# High_Fructose.net
KiCad netlist of a schematic drawn in EAGLE
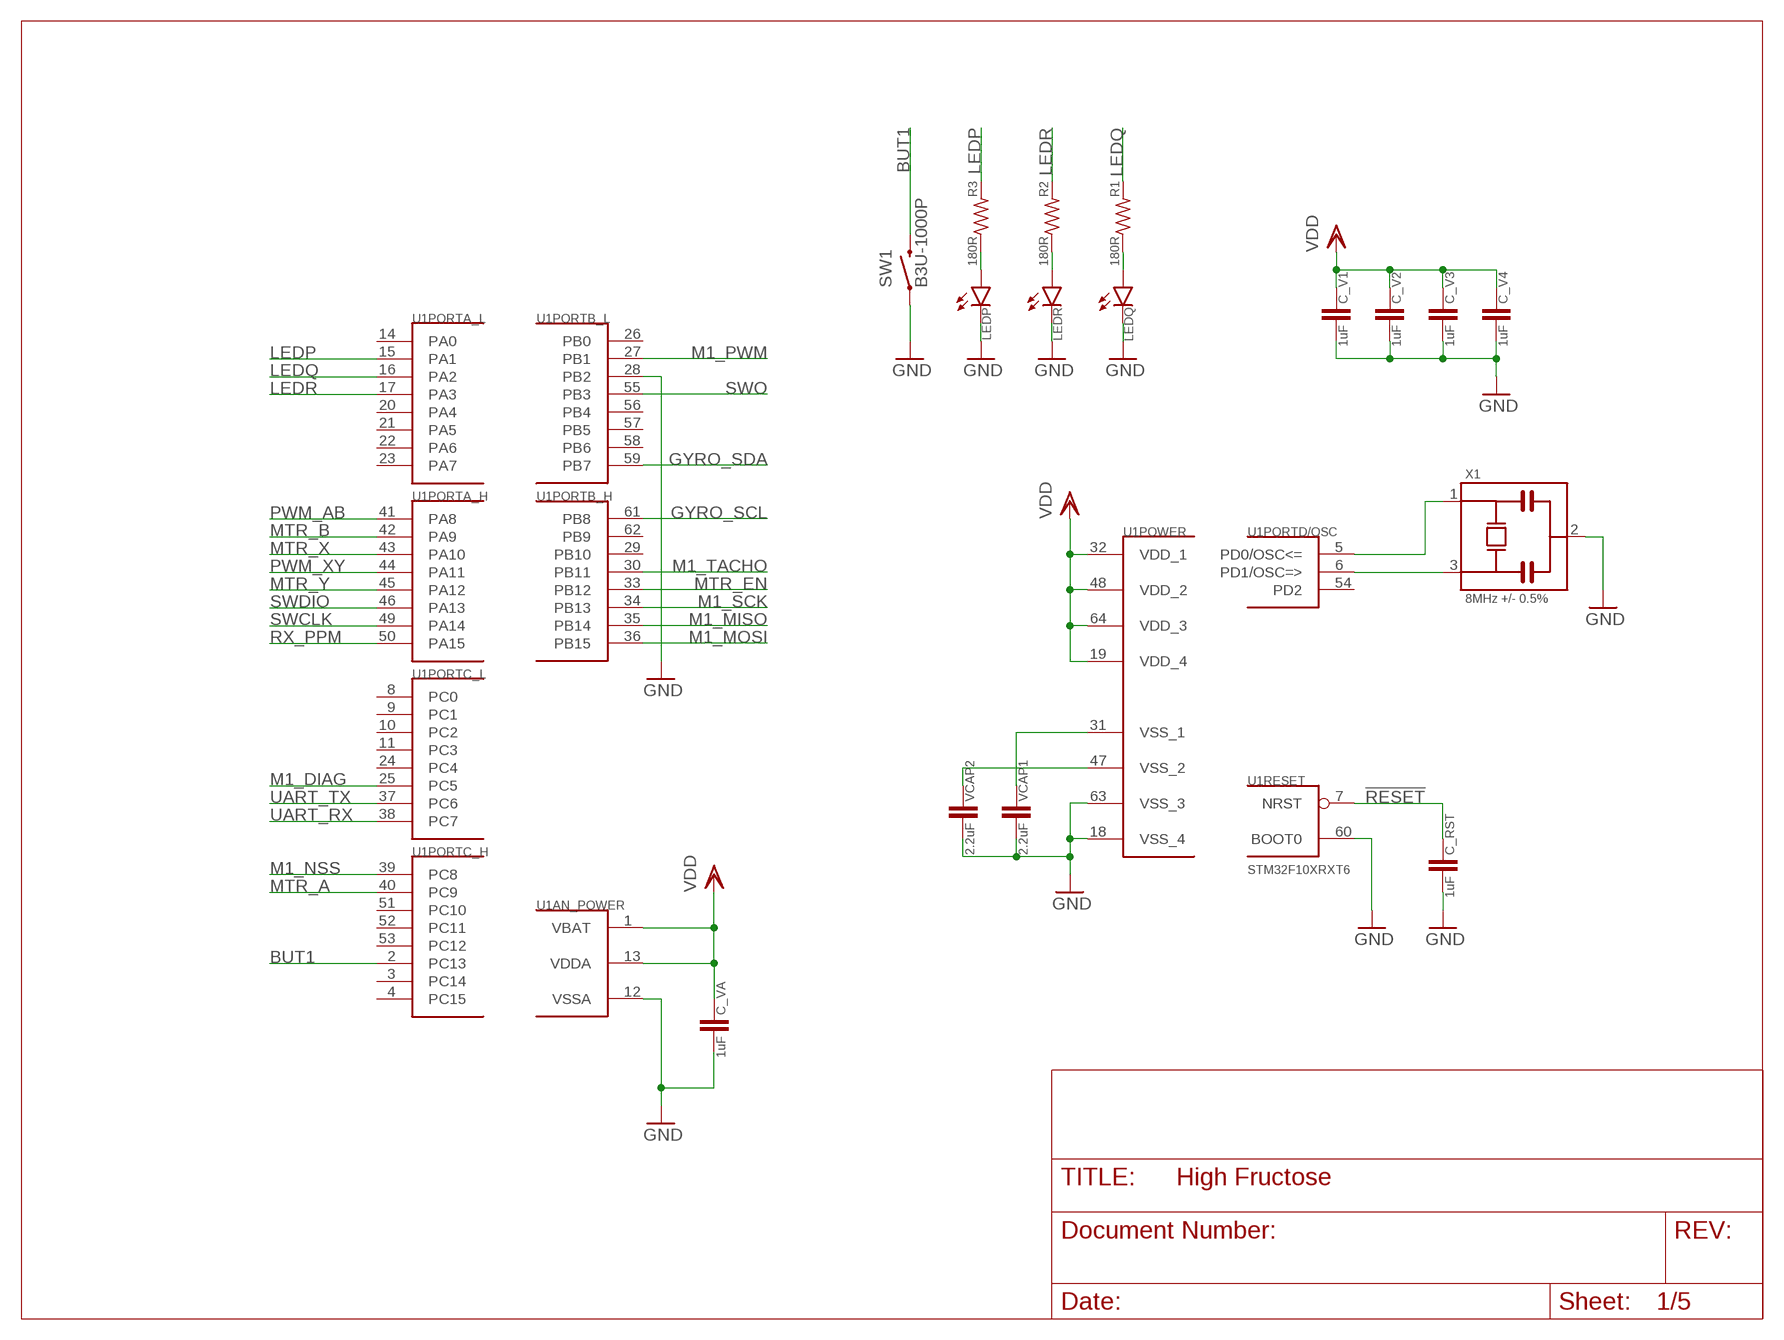
[diagram p0: schematic, sheet 1]
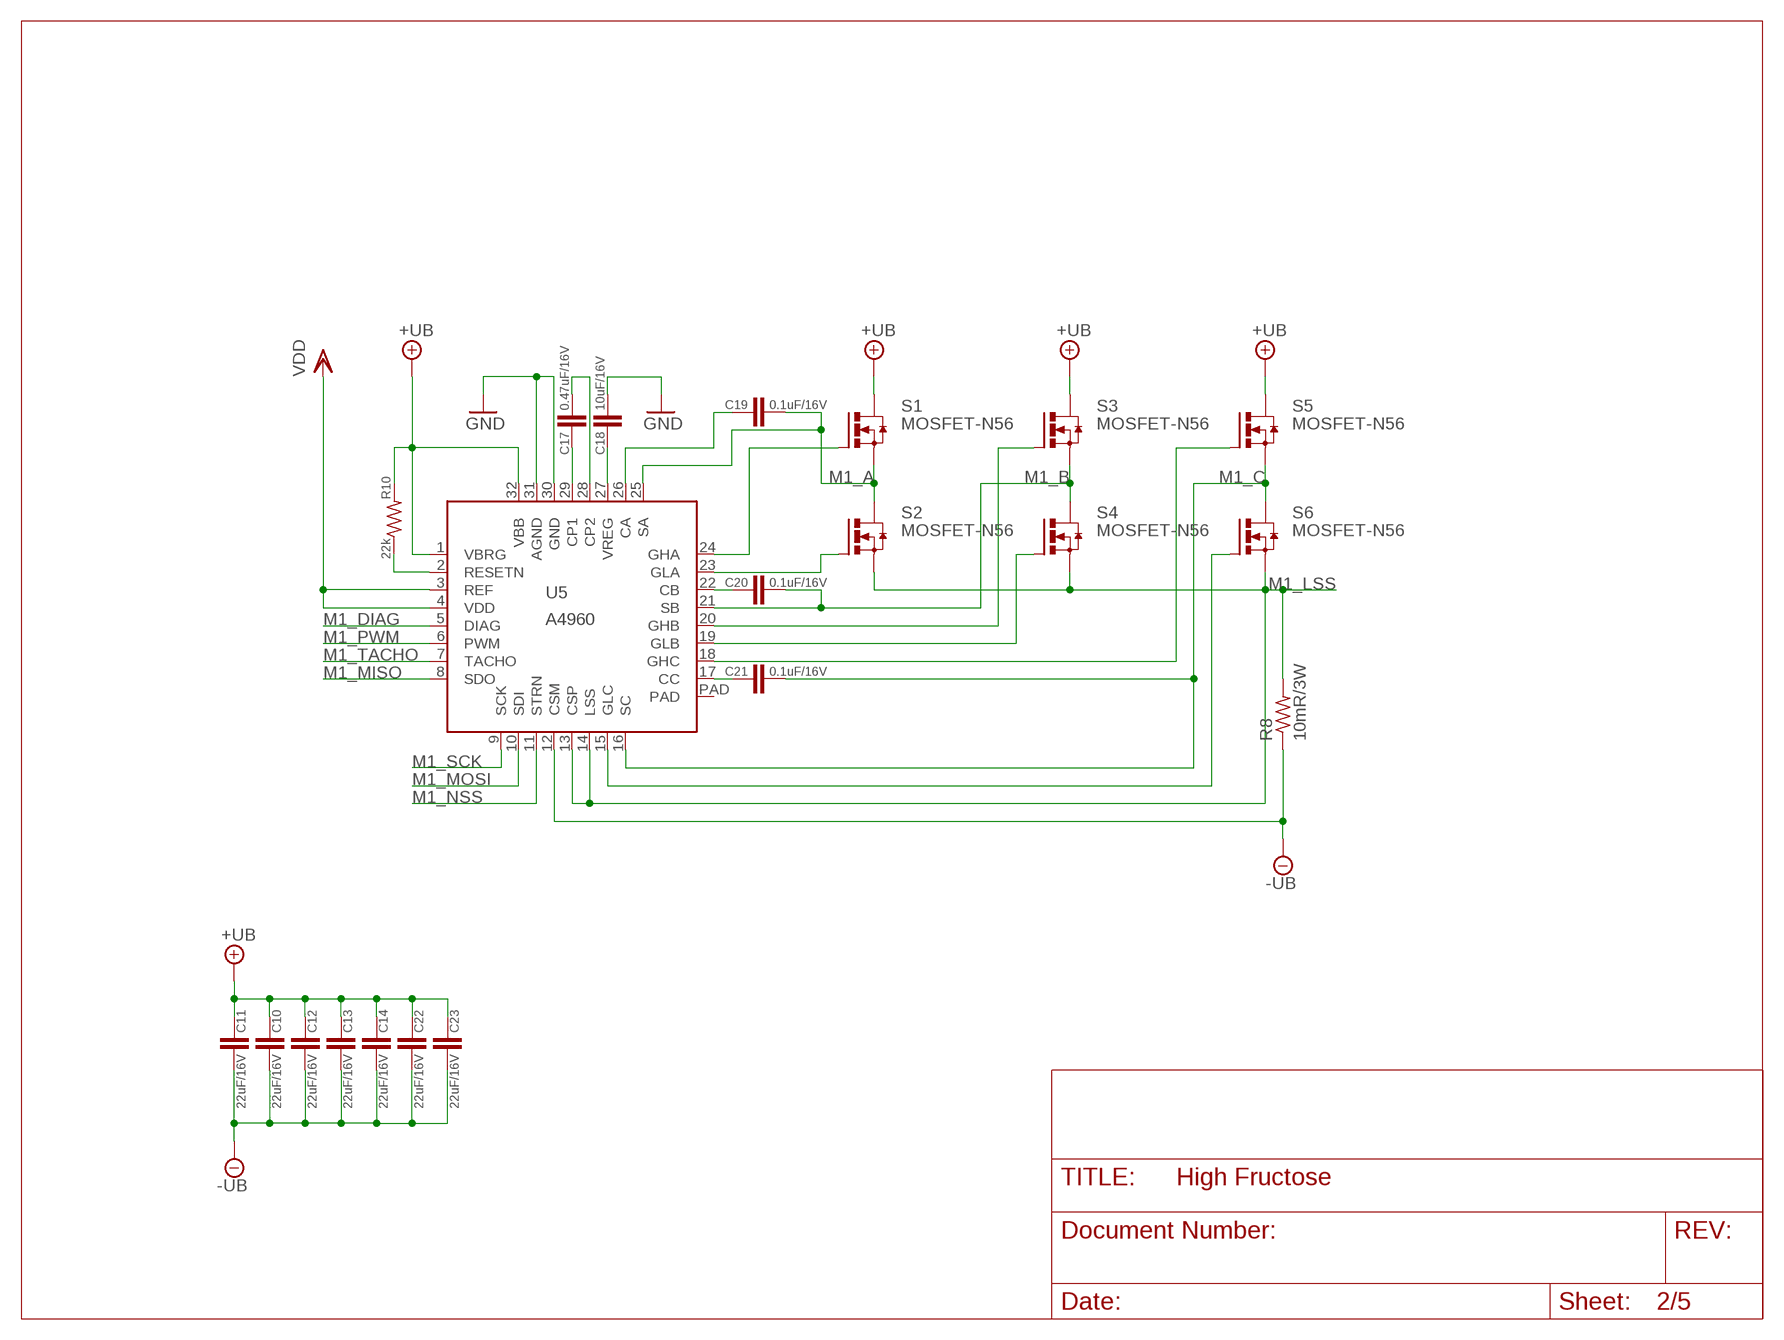
[diagram p1: schematic, sheet 2]
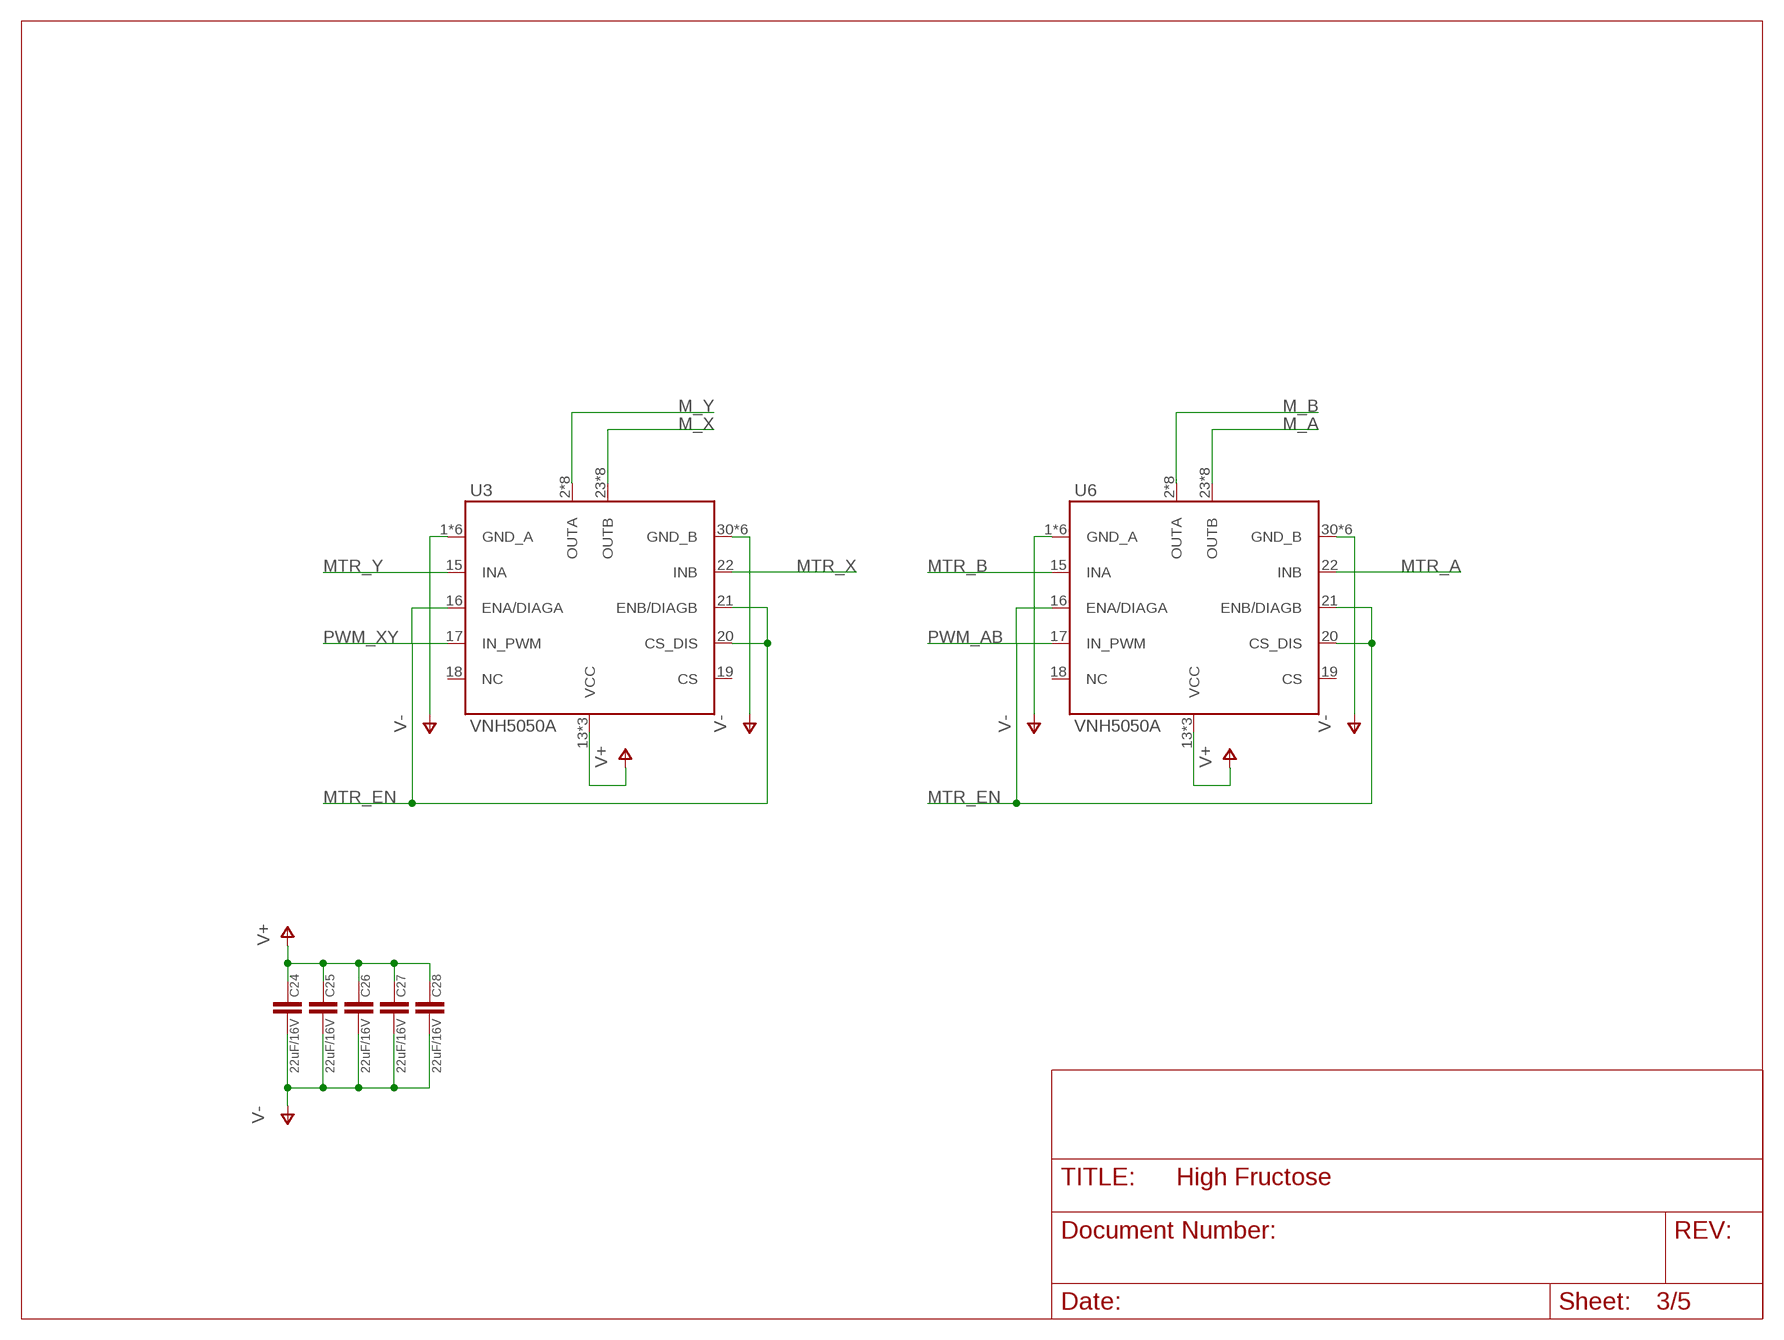
[diagram p2: schematic, sheet 3]
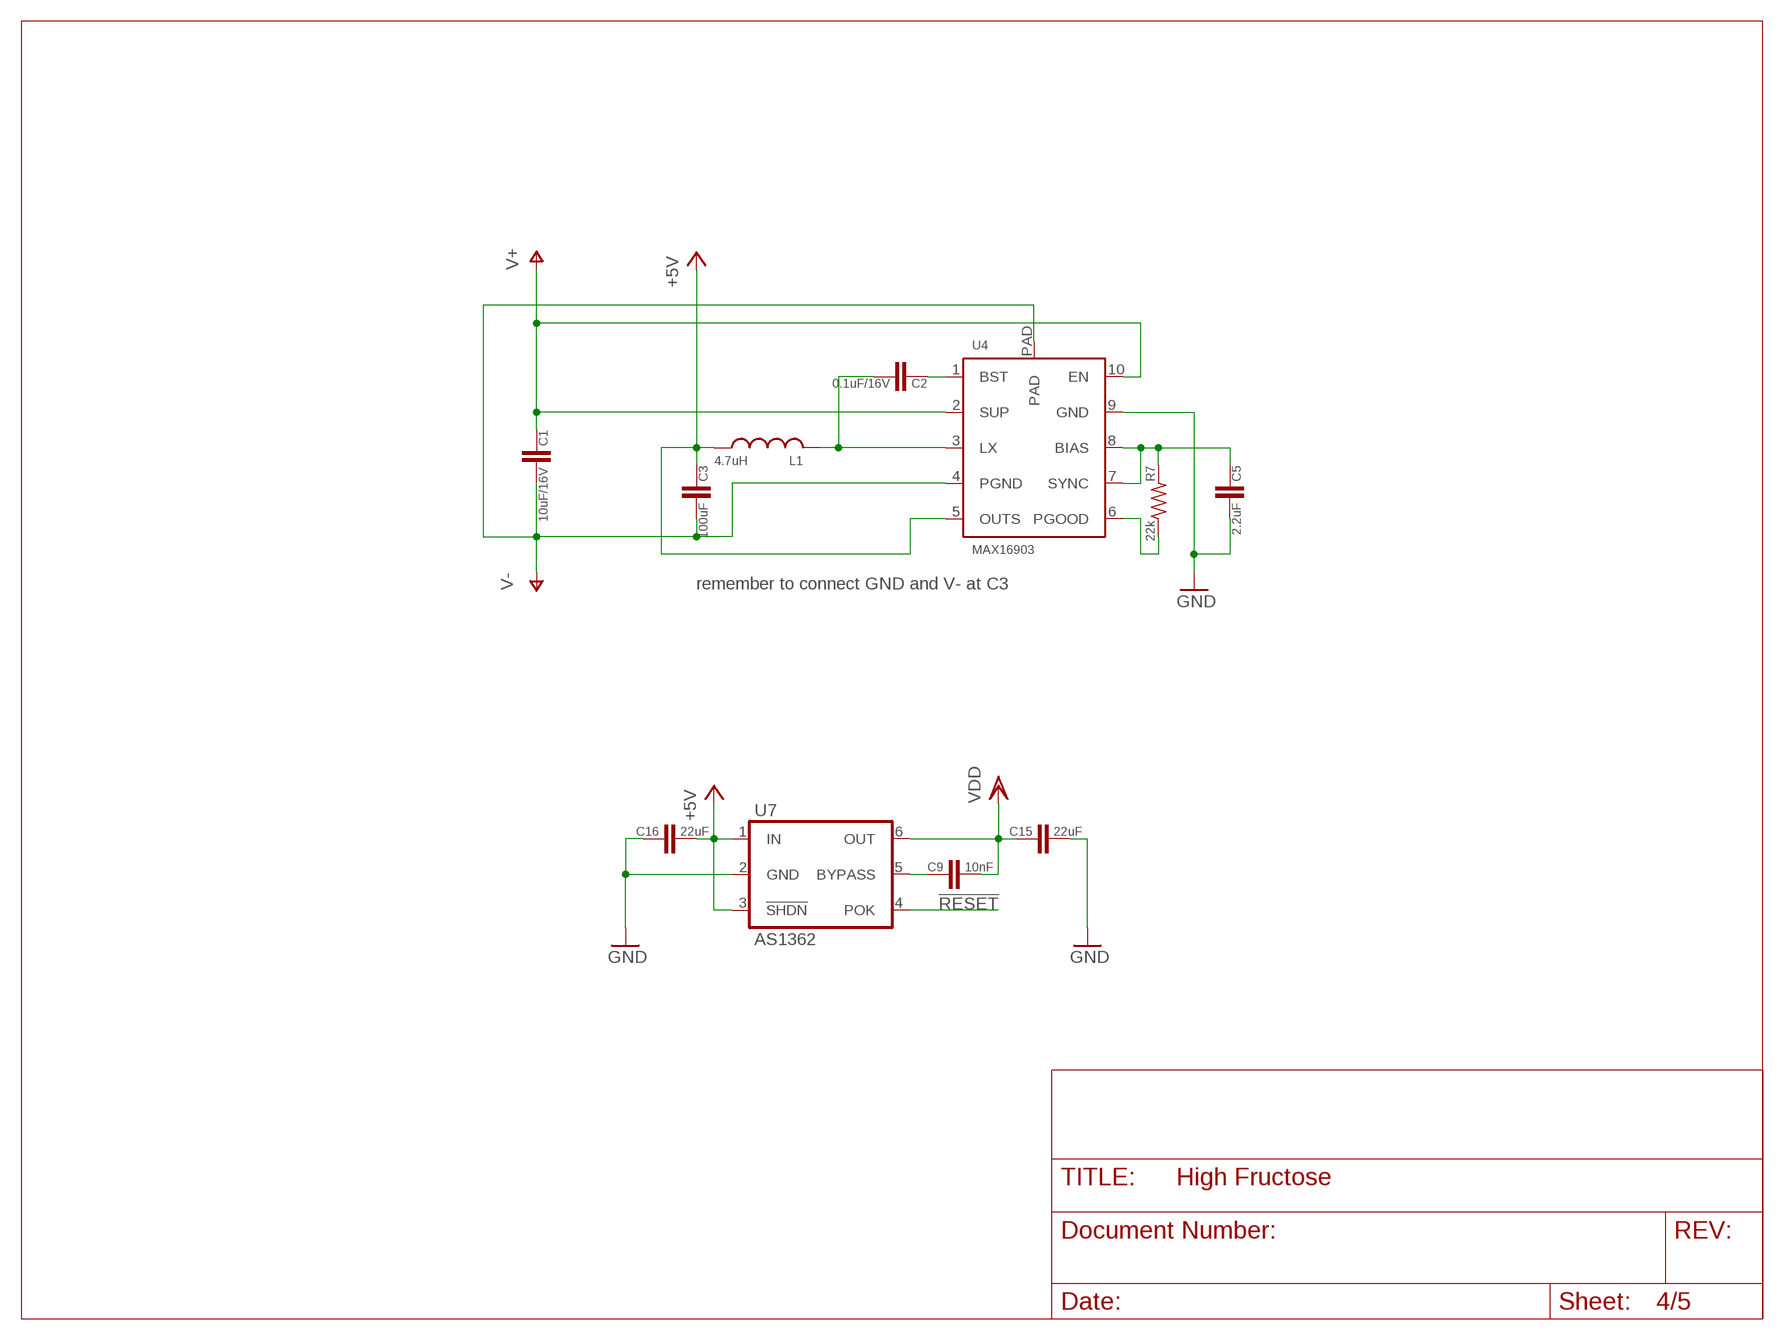
[diagram p3: schematic, sheet 4]
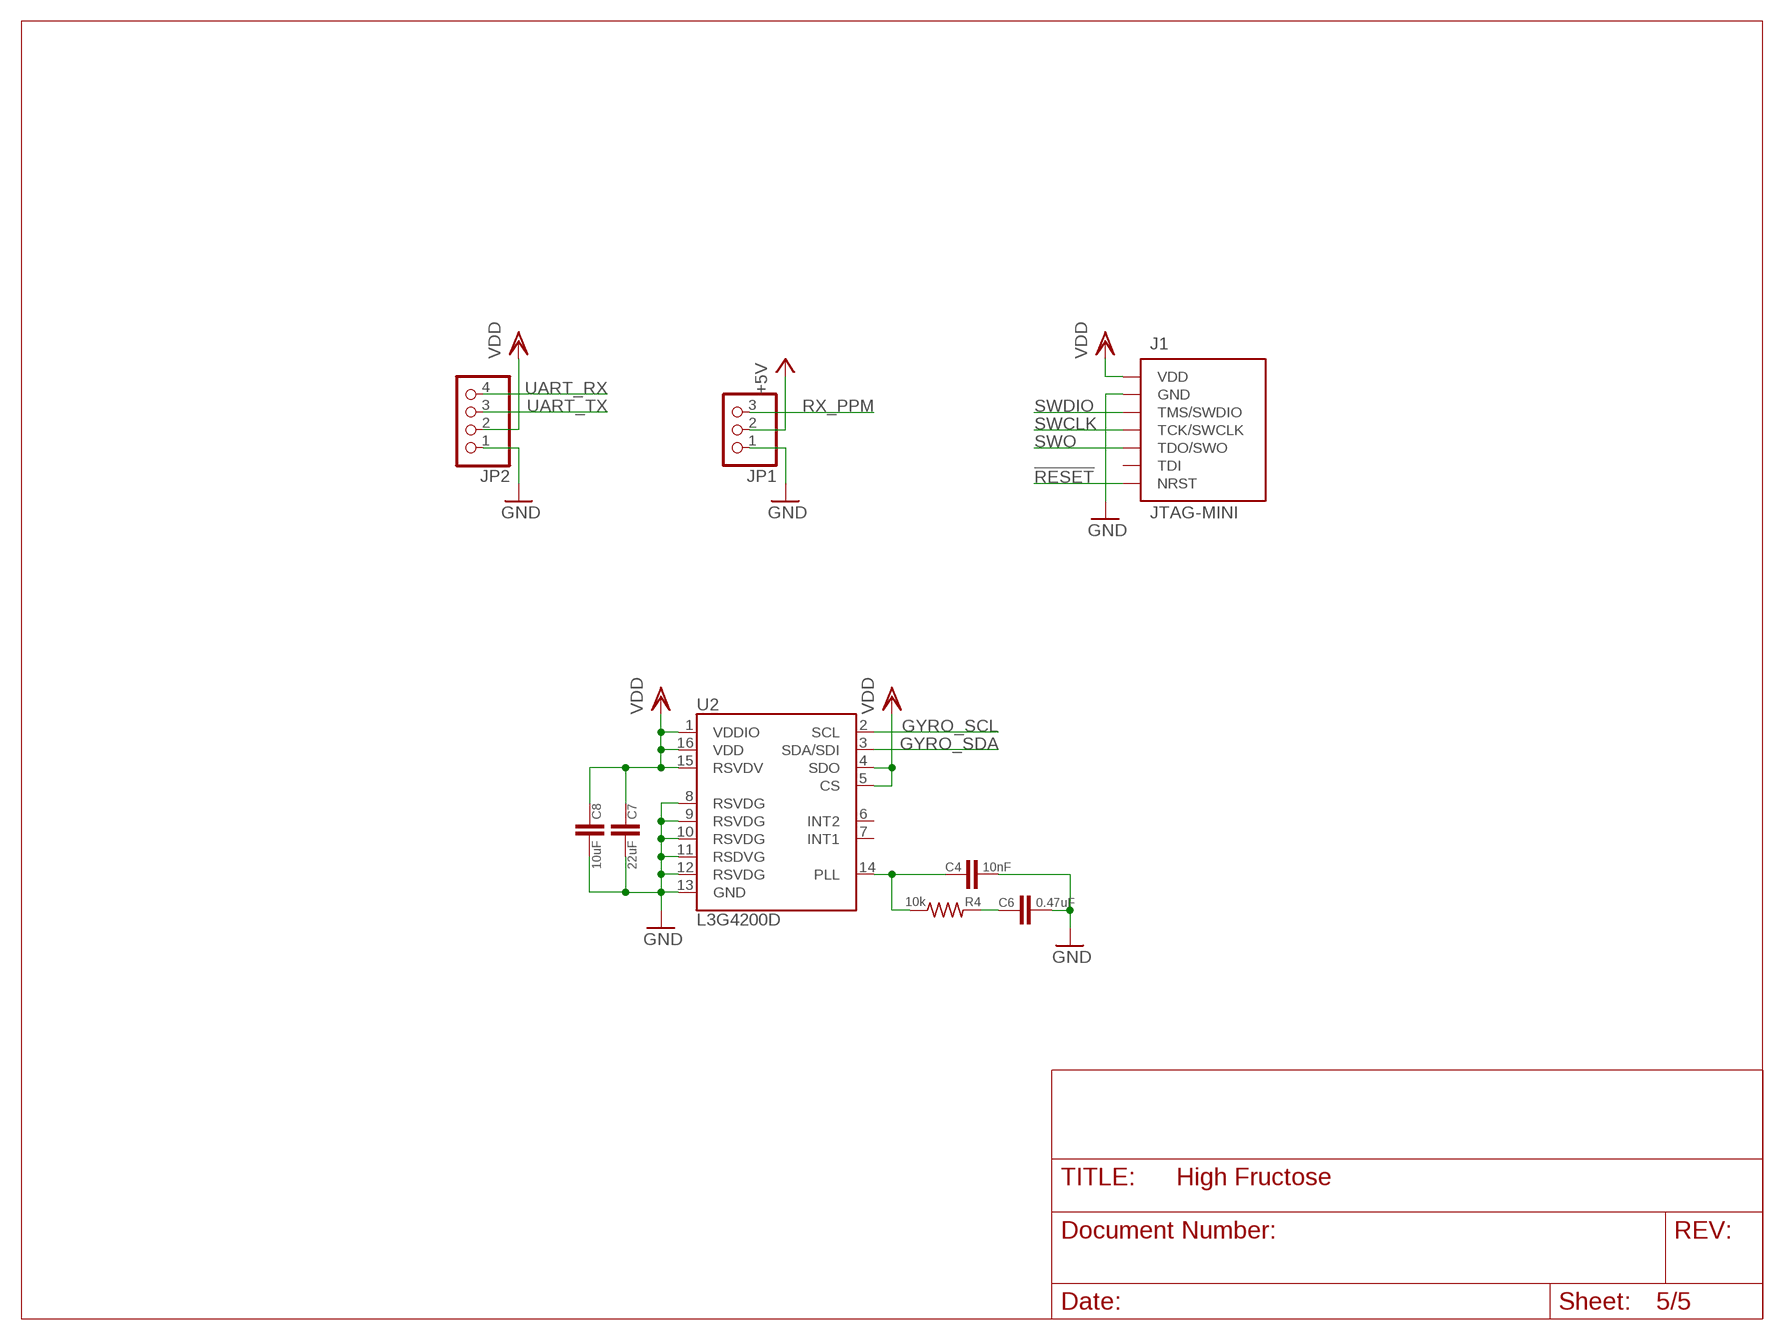
[diagram p4: schematic, sheet 5]

(export (version "E")
  (design (tool "Eeschema 10.0.6"))
  (components
    (comp (ref "C1")
      (value "10uF/16V")
      (footprint "eagle-import:0805")
      (libsource (lib "eagle-import") (part "C0805"))
    )
    (comp (ref "C2")
      (value "0.1uF/16V")
      (footprint "eagle-import:0603")
      (libsource (lib "eagle-import") (part "C0603"))
    )
    (comp (ref "C3")
      (value "100uF")
      (footprint "eagle-import:1206")
      (libsource (lib "eagle-import") (part "C1206"))
    )
    (comp (ref "C5")
      (value "2.2uF")
      (footprint "eagle-import:0603")
      (libsource (lib "eagle-import") (part "C0603"))
    )
    (comp (ref "C9")
      (value "10nF")
      (footprint "eagle-import:0603")
      (libsource (lib "eagle-import") (part "C0603"))
    )
    (comp (ref "C15")
      (value "22uF")
      (footprint "eagle-import:0805")
      (libsource (lib "eagle-import") (part "C0805"))
    )
    (comp (ref "C16")
      (value "22uF")
      (footprint "eagle-import:0805")
      (libsource (lib "eagle-import") (part "C0805"))
    )
    (comp (ref "L1")
      (value "4.7uH")
      (footprint "eagle-import:TAIYO-YUDEN_NR30")
      (libsource (lib "eagle-import") (part "L-US_NR30"))
    )
    (comp (ref "R7")
      (value "22k")
      (footprint "eagle-import:0603")
      (libsource (lib "eagle-import") (part "R0603"))
    )
    (comp (ref "U4")
      (value "MAX16903")
      (footprint "eagle-import:TDFN-10")
      (libsource (lib "eagle-import") (part "MAX16903"))
    )
    (comp (ref "U7")
      (value "AS1362")
      (footprint "eagle-import:SOT23-6")
      (libsource (lib "eagle-import") (part "AS1362"))
    )
    (comp (ref "C24")
      (value "22uF/16V")
      (footprint "eagle-import:1206")
      (libsource (lib "eagle-import") (part "C1206"))
    )
    (comp (ref "C25")
      (value "22uF/16V")
      (footprint "eagle-import:1206")
      (libsource (lib "eagle-import") (part "C1206"))
    )
    (comp (ref "C26")
      (value "22uF/16V")
      (footprint "eagle-import:1206")
      (libsource (lib "eagle-import") (part "C1206"))
    )
    (comp (ref "C27")
      (value "22uF/16V")
      (footprint "eagle-import:1206")
      (libsource (lib "eagle-import") (part "C1206"))
    )
    (comp (ref "C28")
      (value "22uF/16V")
      (footprint "eagle-import:1206")
      (libsource (lib "eagle-import") (part "C1206"))
    )
    (comp (ref "U3")
      (value "VNH5050A")
      (footprint "eagle-import:POWERSSO-36")
      (libsource (lib "eagle-import") (part "VNH5050A"))
    )
    (comp (ref "U6")
      (value "VNH5050A")
      (footprint "eagle-import:POWERSSO-36")
      (libsource (lib "eagle-import") (part "VNH5050A"))
    )
    (comp (ref "C4")
      (value "10nF")
      (footprint "eagle-import:0603")
      (libsource (lib "eagle-import") (part "C0603"))
    )
    (comp (ref "C6")
      (value "0.47uF")
      (footprint "eagle-import:0603")
      (libsource (lib "eagle-import") (part "C0603"))
    )
    (comp (ref "C7")
      (value "22uF")
      (footprint "eagle-import:0805")
      (libsource (lib "eagle-import") (part "C0805"))
    )
    (comp (ref "C8")
      (value "10uF")
      (footprint "eagle-import:0603")
      (libsource (lib "eagle-import") (part "C0603"))
    )
    (comp (ref "J1")
      (value "JTAG-MINI")
      (footprint "eagle-import:JTAG-MINI")
      (libsource (lib "eagle-import") (part "JTAG-MINI"))
    )
    (comp (ref "JP1")
      (value "PINHD-1X03_2.54-S")
      (footprint "eagle-import:1X03-S")
      (libsource (lib "eagle-import") (part "PINHD-1X03_2.54-S"))
    )
    (comp (ref "JP2")
      (value "PINHD-1X04_2.54-S")
      (footprint "eagle-import:1X04-S")
      (libsource (lib "eagle-import") (part "PINHD-1X04_2.54-S"))
    )
    (comp (ref "R4")
      (value "10k")
      (footprint "eagle-import:0603")
      (libsource (lib "eagle-import") (part "R0603"))
    )
    (comp (ref "U2")
      (value "L3G4200D")
      (footprint "eagle-import:LGA16-4X4")
      (libsource (lib "eagle-import") (part "L3G4200D"))
    )
    (comp (ref "C_RST")
      (value "1uF")
      (footprint "eagle-import:0603")
      (libsource (lib "eagle-import") (part "C0603"))
    )
    (comp (ref "C_V1")
      (value "1uF")
      (footprint "eagle-import:0603")
      (libsource (lib "eagle-import") (part "C0603"))
    )
    (comp (ref "C_V2")
      (value "1uF")
      (footprint "eagle-import:0603")
      (libsource (lib "eagle-import") (part "C0603"))
    )
    (comp (ref "C_V3")
      (value "1uF")
      (footprint "eagle-import:0603")
      (libsource (lib "eagle-import") (part "C0603"))
    )
    (comp (ref "C_V4")
      (value "1uF")
      (footprint "eagle-import:0603")
      (libsource (lib "eagle-import") (part "C0603"))
    )
    (comp (ref "C_VA")
      (value "1uF")
      (footprint "eagle-import:0603")
      (libsource (lib "eagle-import") (part "C0603"))
    )
    (comp (ref "LEDP")
      (value "LED0805")
      (footprint "eagle-import:0805_POL")
      (libsource (lib "eagle-import") (part "LED0805"))
    )
    (comp (ref "LEDQ")
      (value "LED0805")
      (footprint "eagle-import:0805_POL")
      (libsource (lib "eagle-import") (part "LED0805"))
    )
    (comp (ref "LEDR")
      (value "LED0805")
      (footprint "eagle-import:0805_POL")
      (libsource (lib "eagle-import") (part "LED0805"))
    )
    (comp (ref "R1")
      (value "180R")
      (footprint "eagle-import:0603")
      (libsource (lib "eagle-import") (part "R0603"))
    )
    (comp (ref "R2")
      (value "180R")
      (footprint "eagle-import:0603")
      (libsource (lib "eagle-import") (part "R0603"))
    )
    (comp (ref "R3")
      (value "180R")
      (footprint "eagle-import:0603")
      (libsource (lib "eagle-import") (part "R0603"))
    )
    (comp (ref "SW1")
      (value "B3U-1000P")
      (footprint "eagle-import:B3U-1000P")
      (libsource (lib "eagle-import") (part "SWITCH_SPST-NOB3U-1000P"))
    )
    (comp (ref "U1")
      (value "STM32F10XRXT6")
      (footprint "eagle-import:TQFP64")
      (libsource (lib "eagle-import") (part "STM32F10XRXT6"))
    )
    (comp (ref "VCAP1")
      (value "2.2uF")
      (footprint "eagle-import:0603")
      (libsource (lib "eagle-import") (part "C0603"))
    )
    (comp (ref "VCAP2")
      (value "2.2uF")
      (footprint "eagle-import:0603")
      (libsource (lib "eagle-import") (part "C0603"))
    )
    (comp (ref "X1")
      (value "8MHz +/- 0.5%")
      (footprint "eagle-import:MURATA_CSTCE")
      (libsource (lib "eagle-import") (part "MURATA_CSTCE"))
    )
    (comp (ref "C10")
      (value "22uF/16V")
      (footprint "eagle-import:1206")
      (libsource (lib "eagle-import") (part "C1206"))
    )
    (comp (ref "C11")
      (value "22uF/16V")
      (footprint "eagle-import:1206")
      (libsource (lib "eagle-import") (part "C1206"))
    )
    (comp (ref "C12")
      (value "22uF/16V")
      (footprint "eagle-import:1206")
      (libsource (lib "eagle-import") (part "C1206"))
    )
    (comp (ref "C13")
      (value "22uF/16V")
      (footprint "eagle-import:1206")
      (libsource (lib "eagle-import") (part "C1206"))
    )
    (comp (ref "C14")
      (value "22uF/16V")
      (footprint "eagle-import:1206")
      (libsource (lib "eagle-import") (part "C1206"))
    )
    (comp (ref "C17")
      (value "0.47uF/16V")
      (footprint "eagle-import:0603")
      (libsource (lib "eagle-import") (part "C0603"))
    )
    (comp (ref "C18")
      (value "10uF/16V")
      (footprint "eagle-import:0805")
      (libsource (lib "eagle-import") (part "C0805"))
    )
    (comp (ref "C19")
      (value "0.1uF/16V")
      (footprint "eagle-import:0603")
      (libsource (lib "eagle-import") (part "C0603"))
    )
    (comp (ref "C20")
      (value "0.1uF/16V")
      (footprint "eagle-import:0603")
      (libsource (lib "eagle-import") (part "C0603"))
    )
    (comp (ref "C21")
      (value "0.1uF/16V")
      (footprint "eagle-import:0603")
      (libsource (lib "eagle-import") (part "C0603"))
    )
    (comp (ref "C22")
      (value "22uF/16V")
      (footprint "eagle-import:1206")
      (libsource (lib "eagle-import") (part "C1206"))
    )
    (comp (ref "C23")
      (value "22uF/16V")
      (footprint "eagle-import:1206")
      (libsource (lib "eagle-import") (part "C1206"))
    )
    (comp (ref "R8")
      (value "10mR/3W")
      (footprint "eagle-import:R2512")
      (libsource (lib "eagle-import") (part "R-US_R2512"))
    )
    (comp (ref "R10")
      (value "22k")
      (footprint "eagle-import:0603")
      (libsource (lib "eagle-import") (part "R0603"))
    )
    (comp (ref "S1")
      (value "MOSFET-N56")
      (footprint "eagle-import:SON-5X6")
      (libsource (lib "eagle-import") (part "MOSFET-N56"))
    )
    (comp (ref "S2")
      (value "MOSFET-N56")
      (footprint "eagle-import:SON-5X6")
      (libsource (lib "eagle-import") (part "MOSFET-N56"))
    )
    (comp (ref "S3")
      (value "MOSFET-N56")
      (footprint "eagle-import:SON-5X6")
      (libsource (lib "eagle-import") (part "MOSFET-N56"))
    )
    (comp (ref "S4")
      (value "MOSFET-N56")
      (footprint "eagle-import:SON-5X6")
      (libsource (lib "eagle-import") (part "MOSFET-N56"))
    )
    (comp (ref "S5")
      (value "MOSFET-N56")
      (footprint "eagle-import:SON-5X6")
      (libsource (lib "eagle-import") (part "MOSFET-N56"))
    )
    (comp (ref "S6")
      (value "MOSFET-N56")
      (footprint "eagle-import:SON-5X6")
      (libsource (lib "eagle-import") (part "MOSFET-N56"))
    )
    (comp (ref "U5")
      (value "A4960")
      (footprint "eagle-import:LQFP32-THERMPAD")
      (libsource (lib "eagle-import") (part "A4960"))
    )
  )
  (nets
    (net (code "1") (name "+5V") (class "Default")
      (node (ref "C16") (pin "2") (pinfunction "2_2") (pintype "passive"))
      (node (ref "C3") (pin "1") (pinfunction "1_1") (pintype "passive"))
      (node (ref "JP1") (pin "2") (pinfunction "2_2") (pintype "passive"))
      (node (ref "L1") (pin "1") (pinfunction "1_1") (pintype "passive"))
      (node (ref "U4") (pin "5") (pinfunction "OUTS_5") (pintype "bidirectional"))
      (node (ref "U7") (pin "1") (pinfunction "IN_1") (pintype "power_in"))
      (node (ref "U7") (pin "3") (pinfunction "~{SHDN}_3") (pintype "input"))
    )
    (net (code "2") (name "+UB") (class "Default")
      (node (ref "C10") (pin "1") (pinfunction "1_1") (pintype "passive"))
      (node (ref "C11") (pin "1") (pinfunction "1_1") (pintype "passive"))
      (node (ref "C12") (pin "1") (pinfunction "1_1") (pintype "passive"))
      (node (ref "C13") (pin "1") (pinfunction "1_1") (pintype "passive"))
      (node (ref "C14") (pin "1") (pinfunction "1_1") (pintype "passive"))
      (node (ref "C22") (pin "1") (pinfunction "1_1") (pintype "passive"))
      (node (ref "C23") (pin "1") (pinfunction "1_1") (pintype "passive"))
      (node (ref "R10") (pin "2") (pinfunction "2_2") (pintype "passive"))
      (node (ref "S1") (pin "D") (pinfunction "D_D") (pintype "passive"))
      (node (ref "S3") (pin "D") (pinfunction "D_D") (pintype "passive"))
      (node (ref "S5") (pin "D") (pinfunction "D_D") (pintype "passive"))
      (node (ref "U5") (pin "1") (pinfunction "VBRG_1") (pintype "bidirectional"))
      (node (ref "U5") (pin "32") (pinfunction "VBB_32") (pintype "power_in"))
    )
    (net (code "3") (name "-UB") (class "Default")
      (node (ref "C10") (pin "2") (pinfunction "2_2") (pintype "passive"))
      (node (ref "C11") (pin "2") (pinfunction "2_2") (pintype "passive"))
      (node (ref "C12") (pin "2") (pinfunction "2_2") (pintype "passive"))
      (node (ref "C13") (pin "2") (pinfunction "2_2") (pintype "passive"))
      (node (ref "C14") (pin "2") (pinfunction "2_2") (pintype "passive"))
      (node (ref "C22") (pin "2") (pinfunction "2_2") (pintype "passive"))
      (node (ref "C23") (pin "2") (pinfunction "2_2") (pintype "passive"))
      (node (ref "R8") (pin "1") (pinfunction "1_1") (pintype "passive"))
      (node (ref "U5") (pin "12") (pinfunction "CSM_12") (pintype "bidirectional"))
    )
    (net (code "4") (name "BUT1") (class "Default")
      (node (ref "SW1") (pin "2") (pinfunction "2_2") (pintype "passive"))
      (node (ref "U1") (pin "2") (pinfunction "PC13_2") (pintype "bidirectional"))
    )
    (net (code "5") (name "GND") (class "Default")
      (node (ref "C15") (pin "2") (pinfunction "2_2") (pintype "passive"))
      (node (ref "C16") (pin "1") (pinfunction "1_1") (pintype "passive"))
      (node (ref "C18") (pin "2") (pinfunction "2_2") (pintype "passive"))
      (node (ref "C4") (pin "2") (pinfunction "2_2") (pintype "passive"))
      (node (ref "C5") (pin "2") (pinfunction "2_2") (pintype "passive"))
      (node (ref "C6") (pin "2") (pinfunction "2_2") (pintype "passive"))
      (node (ref "C7") (pin "2") (pinfunction "2_2") (pintype "passive"))
      (node (ref "C8") (pin "2") (pinfunction "2_2") (pintype "passive"))
      (node (ref "C_RST") (pin "2") (pinfunction "2_2") (pintype "passive"))
      (node (ref "C_V1") (pin "2") (pinfunction "2_2") (pintype "passive"))
      (node (ref "C_V2") (pin "2") (pinfunction "2_2") (pintype "passive"))
      (node (ref "C_V3") (pin "2") (pinfunction "2_2") (pintype "passive"))
      (node (ref "C_V4") (pin "2") (pinfunction "2_2") (pintype "passive"))
      (node (ref "C_VA") (pin "2") (pinfunction "2_2") (pintype "passive"))
      (node (ref "J1") (pin "GND1") (pinfunction "GND_GND1") (pintype "bidirectional"))
      (node (ref "J1") (pin "GND2") (pinfunction "GND_GND2") (pintype "bidirectional"))
      (node (ref "J1") (pin "GND3") (pinfunction "GND_GND3") (pintype "bidirectional"))
      (node (ref "J1") (pin "GND4") (pinfunction "GND_GND4") (pintype "bidirectional"))
      (node (ref "JP1") (pin "1") (pinfunction "1_1") (pintype "passive"))
      (node (ref "JP2") (pin "1") (pinfunction "1_1") (pintype "passive"))
      (node (ref "LEDP") (pin "-") (pinfunction "C_-") (pintype "passive"))
      (node (ref "LEDQ") (pin "-") (pinfunction "C_-") (pintype "passive"))
      (node (ref "LEDR") (pin "-") (pinfunction "C_-") (pintype "passive"))
      (node (ref "SW1") (pin "1") (pinfunction "1_1") (pintype "passive"))
      (node (ref "U1") (pin "12") (pinfunction "VSSA_12") (pintype "power_in"))
      (node (ref "U1") (pin "18") (pinfunction "VSS_4_18") (pintype "power_in"))
      (node (ref "U1") (pin "28") (pinfunction "PB2_28") (pintype "bidirectional"))
      (node (ref "U1") (pin "60") (pinfunction "BOOT0_60") (pintype "input"))
      (node (ref "U1") (pin "63") (pinfunction "VSS_3_63") (pintype "power_in"))
      (node (ref "U2") (pin "10") (pinfunction "RSVDG_10") (pintype "bidirectional"))
      (node (ref "U2") (pin "11") (pinfunction "RSDVG_11") (pintype "bidirectional"))
      (node (ref "U2") (pin "12") (pinfunction "RSVDG_12") (pintype "bidirectional"))
      (node (ref "U2") (pin "13") (pinfunction "GND_13") (pintype "bidirectional"))
      (node (ref "U2") (pin "8") (pinfunction "RSVDG_8") (pintype "bidirectional"))
      (node (ref "U2") (pin "9") (pinfunction "RSVDG_9") (pintype "bidirectional"))
      (node (ref "U4") (pin "9") (pinfunction "GND_9") (pintype "power_in"))
      (node (ref "U5") (pin "30") (pinfunction "GND_30") (pintype "power_in"))
      (node (ref "U5") (pin "31") (pinfunction "AGND_31") (pintype "power_in"))
      (node (ref "U7") (pin "2") (pinfunction "GND_2") (pintype "power_in"))
      (node (ref "VCAP1") (pin "2") (pinfunction "2_2") (pintype "passive"))
      (node (ref "VCAP2") (pin "2") (pinfunction "2_2") (pintype "passive"))
      (node (ref "X1") (pin "2") (pinfunction "P$2_2") (pintype "bidirectional"))
    )
    (net (code "6") (name "GYRO_SCL") (class "Default")
      (node (ref "U1") (pin "61") (pinfunction "PB8_61") (pintype "bidirectional"))
      (node (ref "U2") (pin "2") (pinfunction "SCL_2") (pintype "bidirectional"))
    )
    (net (code "7") (name "GYRO_SDA") (class "Default")
      (node (ref "U1") (pin "59") (pinfunction "PB7_59") (pintype "bidirectional"))
      (node (ref "U2") (pin "3") (pinfunction "SDA/SDI_3") (pintype "bidirectional"))
    )
    (net (code "8") (name "LEDP") (class "Default")
      (node (ref "R3") (pin "2") (pinfunction "2_2") (pintype "passive"))
      (node (ref "U1") (pin "15") (pinfunction "PA1_15") (pintype "bidirectional"))
    )
    (net (code "9") (name "LEDQ") (class "Default")
      (node (ref "R1") (pin "2") (pinfunction "2_2") (pintype "passive"))
      (node (ref "U1") (pin "16") (pinfunction "PA2_16") (pintype "bidirectional"))
    )
    (net (code "10") (name "LEDR") (class "Default")
      (node (ref "R2") (pin "2") (pinfunction "2_2") (pintype "passive"))
      (node (ref "U1") (pin "17") (pinfunction "PA3_17") (pintype "bidirectional"))
    )
    (net (code "11") (name "M1_A") (class "Default")
      (node (ref "C19") (pin "2") (pinfunction "2_2") (pintype "passive"))
      (node (ref "S1") (pin "S1") (pinfunction "S_S1") (pintype "passive"))
      (node (ref "S1") (pin "S2") (pinfunction "S_S2") (pintype "passive"))
      (node (ref "S1") (pin "S3") (pinfunction "S_S3") (pintype "passive"))
      (node (ref "S2") (pin "D") (pinfunction "D_D") (pintype "passive"))
      (node (ref "U5") (pin "25") (pinfunction "SA_25") (pintype "bidirectional"))
    )
    (net (code "12") (name "M1_B") (class "Default")
      (node (ref "C20") (pin "2") (pinfunction "2_2") (pintype "passive"))
      (node (ref "S3") (pin "S1") (pinfunction "S_S1") (pintype "passive"))
      (node (ref "S3") (pin "S2") (pinfunction "S_S2") (pintype "passive"))
      (node (ref "S3") (pin "S3") (pinfunction "S_S3") (pintype "passive"))
      (node (ref "S4") (pin "D") (pinfunction "D_D") (pintype "passive"))
      (node (ref "U5") (pin "21") (pinfunction "SB_21") (pintype "bidirectional"))
    )
    (net (code "13") (name "M1_C") (class "Default")
      (node (ref "C21") (pin "2") (pinfunction "2_2") (pintype "passive"))
      (node (ref "S5") (pin "S1") (pinfunction "S_S1") (pintype "passive"))
      (node (ref "S5") (pin "S2") (pinfunction "S_S2") (pintype "passive"))
      (node (ref "S5") (pin "S3") (pinfunction "S_S3") (pintype "passive"))
      (node (ref "S6") (pin "D") (pinfunction "D_D") (pintype "passive"))
      (node (ref "U5") (pin "16") (pinfunction "SC_16") (pintype "bidirectional"))
    )
    (net (code "14") (name "M1_DIAG") (class "Default")
      (node (ref "U1") (pin "25") (pinfunction "PC5_25") (pintype "bidirectional"))
      (node (ref "U5") (pin "5") (pinfunction "DIAG_5") (pintype "bidirectional"))
    )
    (net (code "15") (name "M1_LSS") (class "Default")
      (node (ref "R8") (pin "2") (pinfunction "2_2") (pintype "passive"))
      (node (ref "S2") (pin "S1") (pinfunction "S_S1") (pintype "passive"))
      (node (ref "S2") (pin "S2") (pinfunction "S_S2") (pintype "passive"))
      (node (ref "S2") (pin "S3") (pinfunction "S_S3") (pintype "passive"))
      (node (ref "S4") (pin "S1") (pinfunction "S_S1") (pintype "passive"))
      (node (ref "S4") (pin "S2") (pinfunction "S_S2") (pintype "passive"))
      (node (ref "S4") (pin "S3") (pinfunction "S_S3") (pintype "passive"))
      (node (ref "S6") (pin "S1") (pinfunction "S_S1") (pintype "passive"))
      (node (ref "S6") (pin "S2") (pinfunction "S_S2") (pintype "passive"))
      (node (ref "S6") (pin "S3") (pinfunction "S_S3") (pintype "passive"))
      (node (ref "U5") (pin "13") (pinfunction "CSP_13") (pintype "bidirectional"))
      (node (ref "U5") (pin "14") (pinfunction "LSS_14") (pintype "bidirectional"))
    )
    (net (code "16") (name "M1_MISO") (class "Default")
      (node (ref "U1") (pin "35") (pinfunction "PB14_35") (pintype "bidirectional"))
      (node (ref "U5") (pin "8") (pinfunction "SDO_8") (pintype "bidirectional"))
    )
    (net (code "17") (name "M1_MOSI") (class "Default")
      (node (ref "U1") (pin "36") (pinfunction "PB15_36") (pintype "bidirectional"))
      (node (ref "U5") (pin "10") (pinfunction "SDI_10") (pintype "input"))
    )
    (net (code "18") (name "M1_NSS") (class "Default")
      (node (ref "U1") (pin "39") (pinfunction "PC8_39") (pintype "bidirectional"))
      (node (ref "U5") (pin "11") (pinfunction "STRN_11") (pintype "input"))
    )
    (net (code "19") (name "M1_PWM") (class "Default")
      (node (ref "U1") (pin "27") (pinfunction "PB1_27") (pintype "bidirectional"))
      (node (ref "U5") (pin "6") (pinfunction "PWM_6") (pintype "input"))
    )
    (net (code "20") (name "M1_SCK") (class "Default")
      (node (ref "U1") (pin "34") (pinfunction "PB13_34") (pintype "bidirectional"))
      (node (ref "U5") (pin "9") (pinfunction "SCK_9") (pintype "input"))
    )
    (net (code "21") (name "M1_TACHO") (class "Default")
      (node (ref "U1") (pin "30") (pinfunction "PB11_30") (pintype "bidirectional"))
      (node (ref "U5") (pin "7") (pinfunction "TACHO_7") (pintype "bidirectional"))
    )
    (net (code "22") (name "MTR_A") (class "Default")
      (node (ref "U1") (pin "40") (pinfunction "PC9_40") (pintype "bidirectional"))
      (node (ref "U6") (pin "22") (pinfunction "INB_22") (pintype "input"))
    )
    (net (code "23") (name "MTR_B") (class "Default")
      (node (ref "U1") (pin "42") (pinfunction "PA9_42") (pintype "bidirectional"))
      (node (ref "U6") (pin "15") (pinfunction "INA_15") (pintype "input"))
    )
    (net (code "24") (name "MTR_EN") (class "Default")
      (node (ref "U1") (pin "33") (pinfunction "PB12_33") (pintype "bidirectional"))
      (node (ref "U3") (pin "16") (pinfunction "ENA/DIAGA_16") (pintype "bidirectional"))
      (node (ref "U3") (pin "20") (pinfunction "CS_DIS_20") (pintype "input"))
      (node (ref "U3") (pin "21") (pinfunction "ENB/DIAGB_21") (pintype "bidirectional"))
      (node (ref "U6") (pin "16") (pinfunction "ENA/DIAGA_16") (pintype "bidirectional"))
      (node (ref "U6") (pin "20") (pinfunction "CS_DIS_20") (pintype "input"))
      (node (ref "U6") (pin "21") (pinfunction "ENB/DIAGB_21") (pintype "bidirectional"))
    )
    (net (code "25") (name "MTR_X") (class "Default")
      (node (ref "U1") (pin "43") (pinfunction "PA10_43") (pintype "bidirectional"))
      (node (ref "U3") (pin "22") (pinfunction "INB_22") (pintype "input"))
    )
    (net (code "26") (name "MTR_Y") (class "Default")
      (node (ref "U1") (pin "45") (pinfunction "PA12_45") (pintype "bidirectional"))
      (node (ref "U3") (pin "15") (pinfunction "INA_15") (pintype "input"))
    )
    (net (code "27") (name "M_A") (class "Default")
      (node (ref "U6") (pin "23") (pinfunction "OUTB_23") (pintype "output"))
      (node (ref "U6") (pin "25") (pinfunction "OUTB_25") (pintype "output"))
      (node (ref "U6") (pin "26") (pinfunction "OUTB_26") (pintype "output"))
      (node (ref "U6") (pin "27") (pinfunction "OUTB_27") (pintype "output"))
      (node (ref "U6") (pin "28") (pinfunction "OUTB_28") (pintype "output"))
      (node (ref "U6") (pin "29") (pinfunction "OUTB_29") (pintype "output"))
      (node (ref "U6") (pin "35") (pinfunction "OUTB_35") (pintype "output"))
      (node (ref "U6") (pin "LS_B") (pinfunction "OUTB_LS_B") (pintype "output"))
    )
    (net (code "28") (name "M_B") (class "Default")
      (node (ref "U6") (pin "10") (pinfunction "OUTA_10") (pintype "output"))
      (node (ref "U6") (pin "11") (pinfunction "OUTA_11") (pintype "output"))
      (node (ref "U6") (pin "12") (pinfunction "OUTA_12") (pintype "output"))
      (node (ref "U6") (pin "14") (pinfunction "OUTA_14") (pintype "output"))
      (node (ref "U6") (pin "2") (pinfunction "OUTA_2") (pintype "output"))
      (node (ref "U6") (pin "8") (pinfunction "OUTA_8") (pintype "output"))
      (node (ref "U6") (pin "9") (pinfunction "OUTA_9") (pintype "output"))
      (node (ref "U6") (pin "LS_A") (pinfunction "OUTA_LS_A") (pintype "output"))
    )
    (net (code "29") (name "M_X") (class "Default")
      (node (ref "U3") (pin "23") (pinfunction "OUTB_23") (pintype "output"))
      (node (ref "U3") (pin "25") (pinfunction "OUTB_25") (pintype "output"))
      (node (ref "U3") (pin "26") (pinfunction "OUTB_26") (pintype "output"))
      (node (ref "U3") (pin "27") (pinfunction "OUTB_27") (pintype "output"))
      (node (ref "U3") (pin "28") (pinfunction "OUTB_28") (pintype "output"))
      (node (ref "U3") (pin "29") (pinfunction "OUTB_29") (pintype "output"))
      (node (ref "U3") (pin "35") (pinfunction "OUTB_35") (pintype "output"))
      (node (ref "U3") (pin "LS_B") (pinfunction "OUTB_LS_B") (pintype "output"))
    )
    (net (code "30") (name "M_Y") (class "Default")
      (node (ref "U3") (pin "10") (pinfunction "OUTA_10") (pintype "output"))
      (node (ref "U3") (pin "11") (pinfunction "OUTA_11") (pintype "output"))
      (node (ref "U3") (pin "12") (pinfunction "OUTA_12") (pintype "output"))
      (node (ref "U3") (pin "14") (pinfunction "OUTA_14") (pintype "output"))
      (node (ref "U3") (pin "2") (pinfunction "OUTA_2") (pintype "output"))
      (node (ref "U3") (pin "8") (pinfunction "OUTA_8") (pintype "output"))
      (node (ref "U3") (pin "9") (pinfunction "OUTA_9") (pintype "output"))
      (node (ref "U3") (pin "LS_A") (pinfunction "OUTA_LS_A") (pintype "output"))
    )
    (net (code "31") (name "Net-(C6-Pad1)") (class "Default")
      (node (ref "C6") (pin "1") (pinfunction "1_1") (pintype "passive"))
      (node (ref "R4") (pin "2") (pinfunction "2_2") (pintype "passive"))
    )
    (net (code "32") (name "Net-(LEDP-A)") (class "Default")
      (node (ref "LEDP") (pin "+") (pinfunction "A_+") (pintype "passive"))
      (node (ref "R3") (pin "1") (pinfunction "1_1") (pintype "passive"))
    )
    (net (code "33") (name "Net-(LEDQ-A)") (class "Default")
      (node (ref "LEDQ") (pin "+") (pinfunction "A_+") (pintype "passive"))
      (node (ref "R1") (pin "1") (pinfunction "1_1") (pintype "passive"))
    )
    (net (code "34") (name "Net-(LEDR-A)") (class "Default")
      (node (ref "LEDR") (pin "+") (pinfunction "A_+") (pintype "passive"))
      (node (ref "R2") (pin "1") (pinfunction "1_1") (pintype "passive"))
    )
    (net (code "35") (name "Net-(U1H-PD0{slash}OSC<=)") (class "Default")
      (node (ref "U1") (pin "5") (pinfunction "PD0/OSC<=_5") (pintype "bidirectional"))
      (node (ref "X1") (pin "1") (pinfunction "P$1_1") (pintype "bidirectional"))
    )
    (net (code "36") (name "Net-(U1H-PD1{slash}OSC=>)") (class "Default")
      (node (ref "U1") (pin "6") (pinfunction "PD1/OSC=>_6") (pintype "bidirectional"))
      (node (ref "X1") (pin "3") (pinfunction "P$3_3") (pintype "bidirectional"))
    )
    (net (code "37") (name "Net-(U1I-VSS_1)") (class "Default")
      (node (ref "U1") (pin "31") (pinfunction "VSS_1_31") (pintype "power_in"))
      (node (ref "VCAP1") (pin "1") (pinfunction "1_1") (pintype "passive"))
    )
    (net (code "38") (name "Net-(U1I-VSS_2)") (class "Default")
      (node (ref "U1") (pin "47") (pinfunction "VSS_2_47") (pintype "power_in"))
      (node (ref "VCAP2") (pin "1") (pinfunction "1_1") (pintype "passive"))
    )
    (net (code "39") (name "Net-(U2-PLL)") (class "Default")
      (node (ref "C4") (pin "1") (pinfunction "1_1") (pintype "passive"))
      (node (ref "R4") (pin "1") (pinfunction "1_1") (pintype "passive"))
      (node (ref "U2") (pin "14") (pinfunction "PLL_14") (pintype "bidirectional"))
    )
    (net (code "40") (name "Net-(U4-BIAS)") (class "Default")
      (node (ref "C5") (pin "1") (pinfunction "1_1") (pintype "passive"))
      (node (ref "R7") (pin "2") (pinfunction "2_2") (pintype "passive"))
      (node (ref "U4") (pin "7") (pinfunction "SYNC_7") (pintype "bidirectional"))
      (node (ref "U4") (pin "8") (pinfunction "BIAS_8") (pintype "bidirectional"))
    )
    (net (code "41") (name "Net-(U4-BST)") (class "Default")
      (node (ref "C2") (pin "1") (pinfunction "1_1") (pintype "passive"))
      (node (ref "U4") (pin "1") (pinfunction "BST_1") (pintype "bidirectional"))
    )
    (net (code "42") (name "Net-(U4-LX)") (class "Default")
      (node (ref "C2") (pin "2") (pinfunction "2_2") (pintype "passive"))
      (node (ref "L1") (pin "2") (pinfunction "2_2") (pintype "passive"))
      (node (ref "U4") (pin "3") (pinfunction "LX_3") (pintype "bidirectional"))
    )
    (net (code "43") (name "Net-(U4-PGOOD)") (class "Default")
      (node (ref "R7") (pin "1") (pinfunction "1_1") (pintype "passive"))
      (node (ref "U4") (pin "6") (pinfunction "PGOOD_6") (pintype "output"))
    )
    (net (code "44") (name "Net-(U5-CA)") (class "Default")
      (node (ref "C19") (pin "1") (pinfunction "1_1") (pintype "passive"))
      (node (ref "U5") (pin "26") (pinfunction "CA_26") (pintype "bidirectional"))
    )
    (net (code "45") (name "Net-(U5-CB)") (class "Default")
      (node (ref "C20") (pin "1") (pinfunction "1_1") (pintype "passive"))
      (node (ref "U5") (pin "22") (pinfunction "CB_22") (pintype "bidirectional"))
    )
    (net (code "46") (name "Net-(U5-CC)") (class "Default")
      (node (ref "C21") (pin "1") (pinfunction "1_1") (pintype "passive"))
      (node (ref "U5") (pin "17") (pinfunction "CC_17") (pintype "bidirectional"))
    )
    (net (code "47") (name "Net-(U5-CP1)") (class "Default")
      (node (ref "C17") (pin "1") (pinfunction "1_1") (pintype "passive"))
      (node (ref "U5") (pin "29") (pinfunction "CP1_29") (pintype "bidirectional"))
    )
    (net (code "48") (name "Net-(U5-CP2)") (class "Default")
      (node (ref "C17") (pin "2") (pinfunction "2_2") (pintype "passive"))
      (node (ref "U5") (pin "28") (pinfunction "CP2_28") (pintype "bidirectional"))
    )
    (net (code "49") (name "Net-(U5-GHA)") (class "Default")
      (node (ref "S1") (pin "G") (pinfunction "G_G") (pintype "passive"))
      (node (ref "U5") (pin "24") (pinfunction "GHA_24") (pintype "bidirectional"))
    )
    (net (code "50") (name "Net-(U5-GHB)") (class "Default")
      (node (ref "S3") (pin "G") (pinfunction "G_G") (pintype "passive"))
      (node (ref "U5") (pin "20") (pinfunction "GHB_20") (pintype "bidirectional"))
    )
    (net (code "51") (name "Net-(U5-GHC)") (class "Default")
      (node (ref "S5") (pin "G") (pinfunction "G_G") (pintype "passive"))
      (node (ref "U5") (pin "18") (pinfunction "GHC_18") (pintype "bidirectional"))
    )
    (net (code "52") (name "Net-(U5-GLA)") (class "Default")
      (node (ref "S2") (pin "G") (pinfunction "G_G") (pintype "passive"))
      (node (ref "U5") (pin "23") (pinfunction "GLA_23") (pintype "bidirectional"))
    )
    (net (code "53") (name "Net-(U5-GLB)") (class "Default")
      (node (ref "S4") (pin "G") (pinfunction "G_G") (pintype "passive"))
      (node (ref "U5") (pin "19") (pinfunction "GLB_19") (pintype "bidirectional"))
    )
    (net (code "54") (name "Net-(U5-GLC)") (class "Default")
      (node (ref "S6") (pin "G") (pinfunction "G_G") (pintype "passive"))
      (node (ref "U5") (pin "15") (pinfunction "GLC_15") (pintype "bidirectional"))
    )
    (net (code "55") (name "Net-(U5-RESETN)") (class "Default")
      (node (ref "R10") (pin "1") (pinfunction "1_1") (pintype "passive"))
      (node (ref "U5") (pin "2") (pinfunction "RESETN_2") (pintype "input"))
    )
    (net (code "56") (name "Net-(U5-VREG)") (class "Default")
      (node (ref "C18") (pin "1") (pinfunction "1_1") (pintype "passive"))
      (node (ref "U5") (pin "27") (pinfunction "VREG_27") (pintype "bidirectional"))
    )
    (net (code "57") (name "Net-(U7-BYPASS)") (class "Default")
      (node (ref "C9") (pin "1") (pinfunction "1_1") (pintype "passive"))
      (node (ref "U7") (pin "5") (pinfunction "BYPASS_5") (pintype "bidirectional"))
    )
    (net (code "58") (name "PWM_AB") (class "Default")
      (node (ref "U1") (pin "41") (pinfunction "PA8_41") (pintype "bidirectional"))
      (node (ref "U6") (pin "17") (pinfunction "IN_PWM_17") (pintype "input"))
    )
    (net (code "59") (name "PWM_XY") (class "Default")
      (node (ref "U1") (pin "44") (pinfunction "PA11_44") (pintype "bidirectional"))
      (node (ref "U3") (pin "17") (pinfunction "IN_PWM_17") (pintype "input"))
    )
    (net (code "60") (name "RX_PPM") (class "Default")
      (node (ref "JP1") (pin "3") (pinfunction "3_3") (pintype "passive"))
      (node (ref "U1") (pin "50") (pinfunction "PA15_50") (pintype "bidirectional"))
    )
    (net (code "61") (name "SWCLK") (class "Default")
      (node (ref "J1") (pin "TCK") (pinfunction "TCK/SWCLK_TCK") (pintype "bidirectional"))
      (node (ref "U1") (pin "49") (pinfunction "PA14_49") (pintype "bidirectional"))
    )
    (net (code "62") (name "SWDIO") (class "Default")
      (node (ref "J1") (pin "TMS") (pinfunction "TMS/SWDIO_TMS") (pintype "bidirectional"))
      (node (ref "U1") (pin "46") (pinfunction "PA13_46") (pintype "bidirectional"))
    )
    (net (code "63") (name "SWO") (class "Default")
      (node (ref "J1") (pin "TDO") (pinfunction "TDO/SWO_TDO") (pintype "bidirectional"))
      (node (ref "U1") (pin "55") (pinfunction "PB3_55") (pintype "bidirectional"))
    )
    (net (code "64") (name "UART_RX") (class "Default")
      (node (ref "JP2") (pin "4") (pinfunction "4_4") (pintype "passive"))
      (node (ref "U1") (pin "38") (pinfunction "PC7_38") (pintype "bidirectional"))
    )
    (net (code "65") (name "UART_TX") (class "Default")
      (node (ref "JP2") (pin "3") (pinfunction "3_3") (pintype "passive"))
      (node (ref "U1") (pin "37") (pinfunction "PC6_37") (pintype "bidirectional"))
    )
    (net (code "66") (name "V+") (class "Default")
      (node (ref "C1") (pin "1") (pinfunction "1_1") (pintype "passive"))
      (node (ref "C24") (pin "1") (pinfunction "1_1") (pintype "passive"))
      (node (ref "C25") (pin "1") (pinfunction "1_1") (pintype "passive"))
      (node (ref "C26") (pin "1") (pinfunction "1_1") (pintype "passive"))
      (node (ref "C27") (pin "1") (pinfunction "1_1") (pintype "passive"))
      (node (ref "C28") (pin "1") (pinfunction "1_1") (pintype "passive"))
      (node (ref "U3") (pin "13") (pinfunction "VCC_13") (pintype "power_in"))
      (node (ref "U3") (pin "24") (pinfunction "VCC_24") (pintype "power_in"))
      (node (ref "U3") (pin "HS_AB") (pinfunction "VCC_HS_AB") (pintype "power_in"))
      (node (ref "U4") (pin "10") (pinfunction "EN_10") (pintype "input"))
      (node (ref "U4") (pin "2") (pinfunction "SUP_2") (pintype "bidirectional"))
      (node (ref "U6") (pin "13") (pinfunction "VCC_13") (pintype "power_in"))
      (node (ref "U6") (pin "24") (pinfunction "VCC_24") (pintype "power_in"))
      (node (ref "U6") (pin "HS_AB") (pinfunction "VCC_HS_AB") (pintype "power_in"))
    )
    (net (code "67") (name "V-") (class "Default")
      (node (ref "C1") (pin "2") (pinfunction "2_2") (pintype "passive"))
      (node (ref "C24") (pin "2") (pinfunction "2_2") (pintype "passive"))
      (node (ref "C25") (pin "2") (pinfunction "2_2") (pintype "passive"))
      (node (ref "C26") (pin "2") (pinfunction "2_2") (pintype "passive"))
      (node (ref "C27") (pin "2") (pinfunction "2_2") (pintype "passive"))
      (node (ref "C28") (pin "2") (pinfunction "2_2") (pintype "passive"))
      (node (ref "C3") (pin "2") (pinfunction "2_2") (pintype "passive"))
      (node (ref "U3") (pin "1") (pinfunction "GND_A_1") (pintype "power_in"))
      (node (ref "U3") (pin "3") (pinfunction "GND_A_3") (pintype "power_in"))
      (node (ref "U3") (pin "30") (pinfunction "GND_B_30") (pintype "power_in"))
      (node (ref "U3") (pin "31") (pinfunction "GND_B_31") (pintype "power_in"))
      (node (ref "U3") (pin "32") (pinfunction "GND_B_32") (pintype "power_in"))
      (node (ref "U3") (pin "33") (pinfunction "GND_B_33") (pintype "power_in"))
      (node (ref "U3") (pin "34") (pinfunction "GND_B_34") (pintype "power_in"))
      (node (ref "U3") (pin "36") (pinfunction "GND_B_36") (pintype "power_in"))
      (node (ref "U3") (pin "4") (pinfunction "GND_A_4") (pintype "power_in"))
      (node (ref "U3") (pin "5") (pinfunction "GND_A_5") (pintype "power_in"))
      (node (ref "U3") (pin "6") (pinfunction "GND_A_6") (pintype "power_in"))
      (node (ref "U3") (pin "7") (pinfunction "GND_A_7") (pintype "power_in"))
      (node (ref "U4") (pin "4") (pinfunction "PGND_4") (pintype "power_in"))
      (node (ref "U4") (pin "PAD") (pinfunction "PAD_PAD") (pintype "power_in"))
      (node (ref "U6") (pin "1") (pinfunction "GND_A_1") (pintype "power_in"))
      (node (ref "U6") (pin "3") (pinfunction "GND_A_3") (pintype "power_in"))
      (node (ref "U6") (pin "30") (pinfunction "GND_B_30") (pintype "power_in"))
      (node (ref "U6") (pin "31") (pinfunction "GND_B_31") (pintype "power_in"))
      (node (ref "U6") (pin "32") (pinfunction "GND_B_32") (pintype "power_in"))
      (node (ref "U6") (pin "33") (pinfunction "GND_B_33") (pintype "power_in"))
      (node (ref "U6") (pin "34") (pinfunction "GND_B_34") (pintype "power_in"))
      (node (ref "U6") (pin "36") (pinfunction "GND_B_36") (pintype "power_in"))
      (node (ref "U6") (pin "4") (pinfunction "GND_A_4") (pintype "power_in"))
      (node (ref "U6") (pin "5") (pinfunction "GND_A_5") (pintype "power_in"))
      (node (ref "U6") (pin "6") (pinfunction "GND_A_6") (pintype "power_in"))
      (node (ref "U6") (pin "7") (pinfunction "GND_A_7") (pintype "power_in"))
    )
    (net (code "68") (name "VDD") (class "Default")
      (node (ref "C15") (pin "1") (pinfunction "1_1") (pintype "passive"))
      (node (ref "C7") (pin "1") (pinfunction "1_1") (pintype "passive"))
      (node (ref "C8") (pin "1") (pinfunction "1_1") (pintype "passive"))
      (node (ref "C9") (pin "2") (pinfunction "2_2") (pintype "passive"))
      (node (ref "C_V1") (pin "1") (pinfunction "1_1") (pintype "passive"))
      (node (ref "C_V2") (pin "1") (pinfunction "1_1") (pintype "passive"))
      (node (ref "C_V3") (pin "1") (pinfunction "1_1") (pintype "passive"))
      (node (ref "C_V4") (pin "1") (pinfunction "1_1") (pintype "passive"))
      (node (ref "C_VA") (pin "1") (pinfunction "1_1") (pintype "passive"))
      (node (ref "J1") (pin "VDD") (pinfunction "VDD_VDD") (pintype "bidirectional"))
      (node (ref "JP2") (pin "2") (pinfunction "2_2") (pintype "passive"))
      (node (ref "U1") (pin "1") (pinfunction "VBAT_1") (pintype "power_in"))
      (node (ref "U1") (pin "13") (pinfunction "VDDA_13") (pintype "power_in"))
      (node (ref "U1") (pin "19") (pinfunction "VDD_4_19") (pintype "power_in"))
      (node (ref "U1") (pin "32") (pinfunction "VDD_1_32") (pintype "power_in"))
      (node (ref "U1") (pin "48") (pinfunction "VDD_2_48") (pintype "power_in"))
      (node (ref "U1") (pin "64") (pinfunction "VDD_3_64") (pintype "power_in"))
      (node (ref "U2") (pin "1") (pinfunction "VDDIO_1") (pintype "bidirectional"))
      (node (ref "U2") (pin "15") (pinfunction "RSVDV_15") (pintype "bidirectional"))
      (node (ref "U2") (pin "16") (pinfunction "VDD_16") (pintype "bidirectional"))
      (node (ref "U2") (pin "4") (pinfunction "SDO_4") (pintype "bidirectional"))
      (node (ref "U2") (pin "5") (pinfunction "CS_5") (pintype "bidirectional"))
      (node (ref "U5") (pin "3") (pinfunction "REF_3") (pintype "bidirectional"))
      (node (ref "U5") (pin "4") (pinfunction "VDD_4") (pintype "power_in"))
      (node (ref "U7") (pin "6") (pinfunction "OUT_6") (pintype "power_in"))
    )
    (net (code "69") (name "unconnected-(J1-PadTDI)") (class "Default")
      (node (ref "J1") (pin "TDI") (pinfunction "TDI_TDI") (pintype "bidirectional"))
    )
    (net (code "70") (name "unconnected-(U1C-PA0-Pad14)") (class "Default")
      (node (ref "U1") (pin "14") (pinfunction "PA0_14") (pintype "bidirectional"))
    )
    (net (code "71") (name "unconnected-(U1C-PA4-Pad20)") (class "Default")
      (node (ref "U1") (pin "20") (pinfunction "PA4_20") (pintype "bidirectional"))
    )
    (net (code "72") (name "unconnected-(U1C-PA5-Pad21)") (class "Default")
      (node (ref "U1") (pin "21") (pinfunction "PA5_21") (pintype "bidirectional"))
    )
    (net (code "73") (name "unconnected-(U1C-PA6-Pad22)") (class "Default")
      (node (ref "U1") (pin "22") (pinfunction "PA6_22") (pintype "bidirectional"))
    )
    (net (code "74") (name "unconnected-(U1C-PA7-Pad23)") (class "Default")
      (node (ref "U1") (pin "23") (pinfunction "PA7_23") (pintype "bidirectional"))
    )
    (net (code "75") (name "unconnected-(U1D-PB9-Pad62)") (class "Default")
      (node (ref "U1") (pin "62") (pinfunction "PB9_62") (pintype "bidirectional"))
    )
    (net (code "76") (name "unconnected-(U1D-PB10-Pad29)") (class "Default")
      (node (ref "U1") (pin "29") (pinfunction "PB10_29") (pintype "bidirectional"))
    )
    (net (code "77") (name "unconnected-(U1E-PB0-Pad26)") (class "Default")
      (node (ref "U1") (pin "26") (pinfunction "PB0_26") (pintype "bidirectional"))
    )
    (net (code "78") (name "unconnected-(U1E-PB4-Pad56)") (class "Default")
      (node (ref "U1") (pin "56") (pinfunction "PB4_56") (pintype "bidirectional"))
    )
    (net (code "79") (name "unconnected-(U1E-PB5-Pad57)") (class "Default")
      (node (ref "U1") (pin "57") (pinfunction "PB5_57") (pintype "bidirectional"))
    )
    (net (code "80") (name "unconnected-(U1E-PB6-Pad58)") (class "Default")
      (node (ref "U1") (pin "58") (pinfunction "PB6_58") (pintype "bidirectional"))
    )
    (net (code "81") (name "unconnected-(U1F-PC10-Pad51)") (class "Default")
      (node (ref "U1") (pin "51") (pinfunction "PC10_51") (pintype "bidirectional"))
    )
    (net (code "82") (name "unconnected-(U1F-PC11-Pad52)") (class "Default")
      (node (ref "U1") (pin "52") (pinfunction "PC11_52") (pintype "bidirectional"))
    )
    (net (code "83") (name "unconnected-(U1F-PC12-Pad53)") (class "Default")
      (node (ref "U1") (pin "53") (pinfunction "PC12_53") (pintype "bidirectional"))
    )
    (net (code "84") (name "unconnected-(U1F-PC14-Pad3)") (class "Default")
      (node (ref "U1") (pin "3") (pinfunction "PC14_3") (pintype "bidirectional"))
    )
    (net (code "85") (name "unconnected-(U1F-PC15-Pad4)") (class "Default")
      (node (ref "U1") (pin "4") (pinfunction "PC15_4") (pintype "bidirectional"))
    )
    (net (code "86") (name "unconnected-(U1G-PC0-Pad8)") (class "Default")
      (node (ref "U1") (pin "8") (pinfunction "PC0_8") (pintype "bidirectional"))
    )
    (net (code "87") (name "unconnected-(U1G-PC1-Pad9)") (class "Default")
      (node (ref "U1") (pin "9") (pinfunction "PC1_9") (pintype "bidirectional"))
    )
    (net (code "88") (name "unconnected-(U1G-PC2-Pad10)") (class "Default")
      (node (ref "U1") (pin "10") (pinfunction "PC2_10") (pintype "bidirectional"))
    )
    (net (code "89") (name "unconnected-(U1G-PC3-Pad11)") (class "Default")
      (node (ref "U1") (pin "11") (pinfunction "PC3_11") (pintype "bidirectional"))
    )
    (net (code "90") (name "unconnected-(U1G-PC4-Pad24)") (class "Default")
      (node (ref "U1") (pin "24") (pinfunction "PC4_24") (pintype "bidirectional"))
    )
    (net (code "91") (name "unconnected-(U1H-PD2-Pad54)") (class "Default")
      (node (ref "U1") (pin "54") (pinfunction "PD2_54") (pintype "bidirectional"))
    )
    (net (code "92") (name "unconnected-(U2-INT1-Pad7)") (class "Default")
      (node (ref "U2") (pin "7") (pinfunction "INT1_7") (pintype "bidirectional"))
    )
    (net (code "93") (name "unconnected-(U2-INT2-Pad6)") (class "Default")
      (node (ref "U2") (pin "6") (pinfunction "INT2_6") (pintype "bidirectional"))
    )
    (net (code "94") (name "unconnected-(U3-CS-Pad19)") (class "Default")
      (node (ref "U3") (pin "19") (pinfunction "CS_19") (pintype "output"))
    )
    (net (code "95") (name "unconnected-(U3-NC-Pad18)") (class "Default")
      (node (ref "U3") (pin "18") (pinfunction "NC_18") (pintype "no_connect"))
    )
    (net (code "96") (name "unconnected-(U5-PadPAD)") (class "Default")
      (node (ref "U5") (pin "PAD") (pinfunction "PAD_PAD") (pintype "bidirectional"))
    )
    (net (code "97") (name "unconnected-(U6-CS-Pad19)") (class "Default")
      (node (ref "U6") (pin "19") (pinfunction "CS_19") (pintype "output"))
    )
    (net (code "98") (name "unconnected-(U6-NC-Pad18)") (class "Default")
      (node (ref "U6") (pin "18") (pinfunction "NC_18") (pintype "no_connect"))
    )
    (net (code "99") (name "~{RESET}") (class "Default")
      (node (ref "C_RST") (pin "1") (pinfunction "1_1") (pintype "passive"))
      (node (ref "J1") (pin "NRST") (pinfunction "NRST_NRST") (pintype "bidirectional"))
      (node (ref "U1") (pin "7") (pinfunction "NRST_7") (pintype "input"))
      (node (ref "U7") (pin "4") (pinfunction "POK_4") (pintype "output"))
    )
  )
)
